# EXT_LED_RGB_NPN.net
KiCad netlist of a schematic drawn in EAGLE
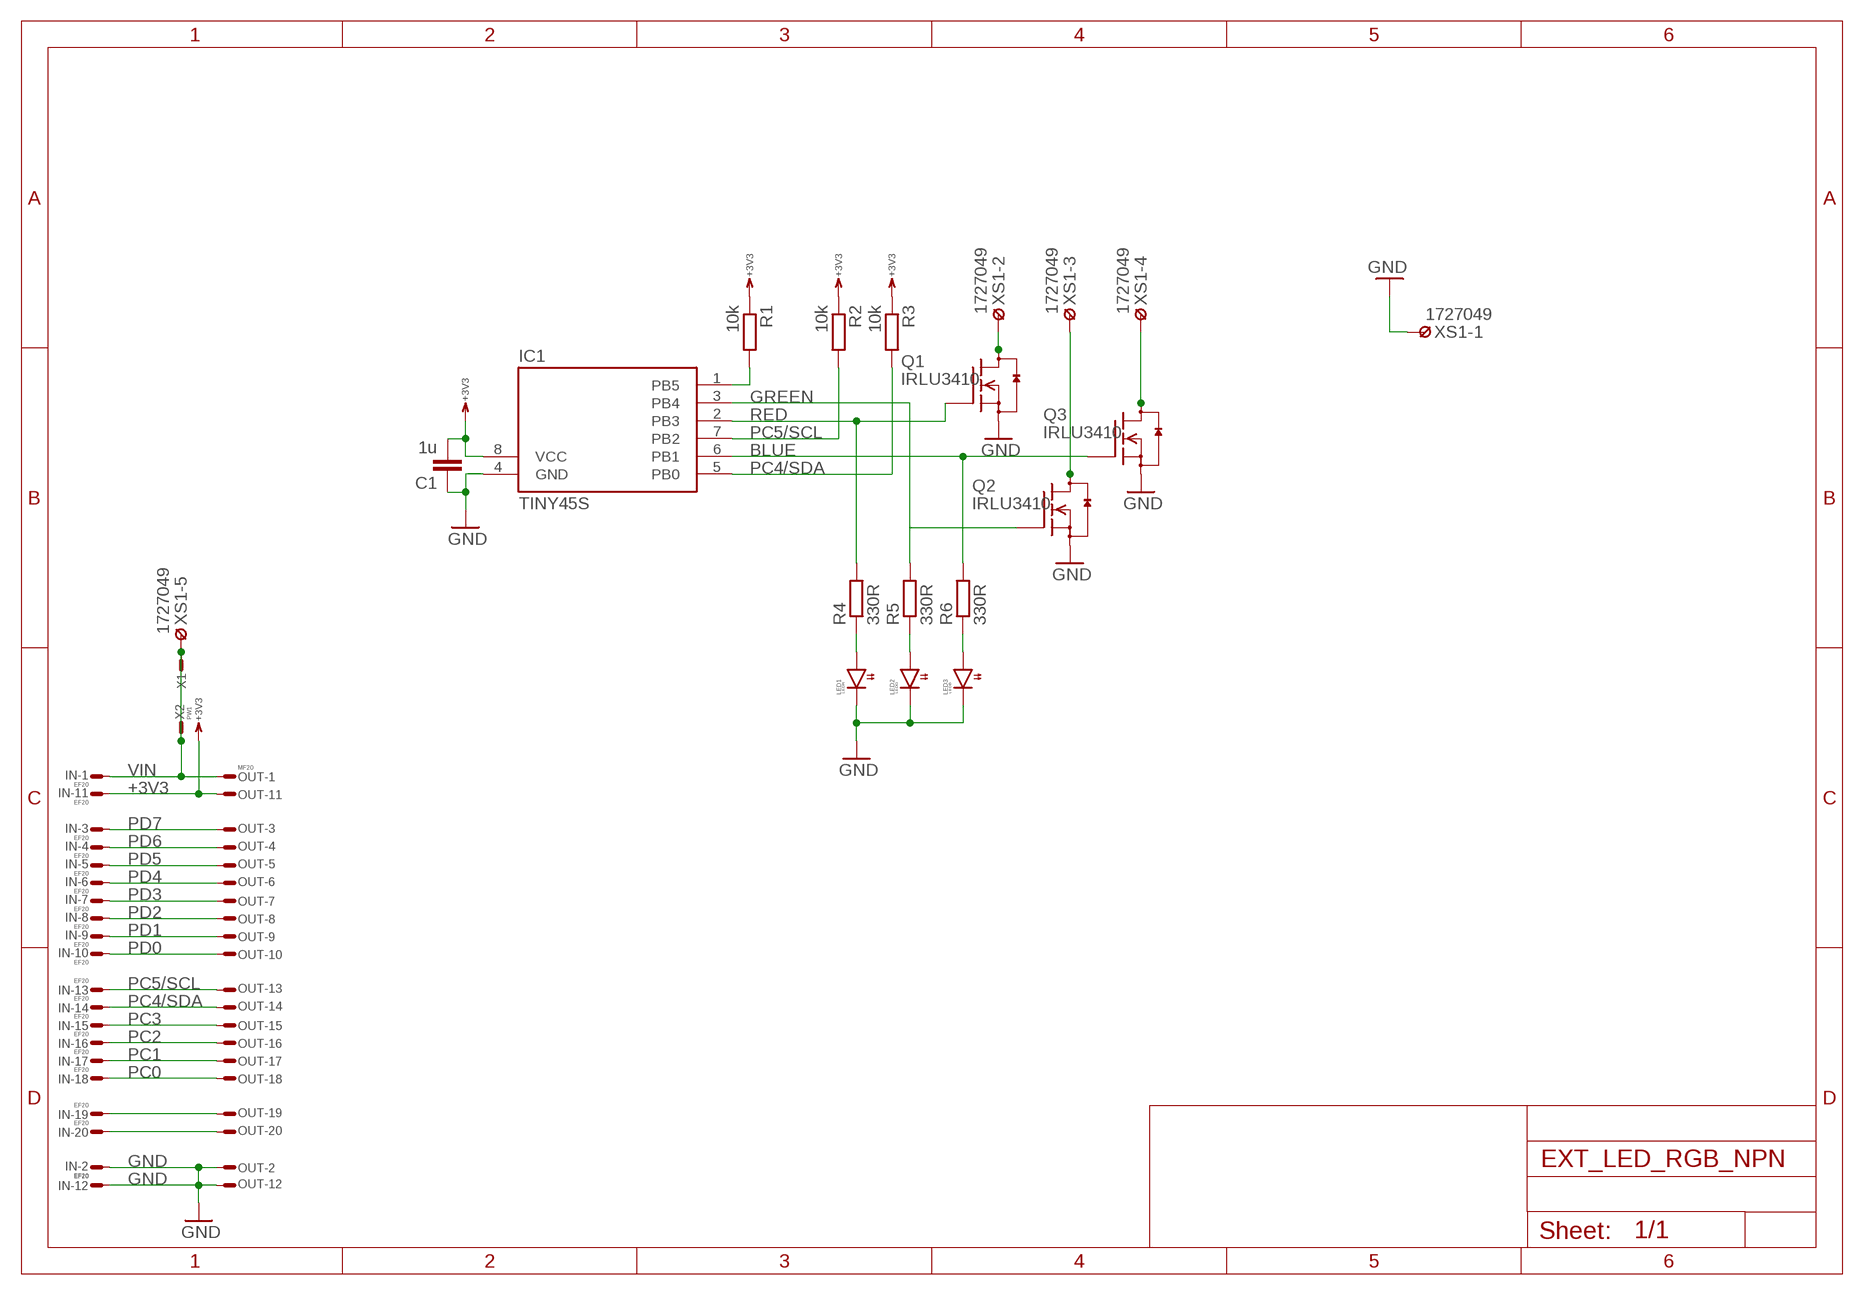
[diagram p0: schematic, sheet 1]

(export (version "E")
  (design (tool "Eeschema 10.0.6"))
  (components
    (comp (ref "C1")
      (value "1u")
      (footprint "eagle-import:0603")
      (libsource (lib "eagle-import") (part "C0603"))
    )
    (comp (ref "IC1")
      (value "TINY45S")
      (footprint "eagle-import:SOIC8")
      (libsource (lib "eagle-import") (part "TINY45S"))
    )
    (comp (ref "IN")
      (value "EF20")
      (footprint "eagle-import:FE10-2WSS")
      (libsource (lib "eagle-import") (part "FE20ELSS"))
    )
    (comp (ref "LED1")
      (value "LEDR")
      (footprint "eagle-import:1206")
      (libsource (lib "eagle-import") (part "LED1206"))
    )
    (comp (ref "LED2")
      (value "LEDG")
      (footprint "eagle-import:1206")
      (libsource (lib "eagle-import") (part "LED1206"))
    )
    (comp (ref "LED3")
      (value "LEDB")
      (footprint "eagle-import:1206")
      (libsource (lib "eagle-import") (part "LED1206"))
    )
    (comp (ref "OUT")
      (value "MF20")
      (footprint "eagle-import:ML20LS")
      (libsource (lib "eagle-import") (part "ML20?ELS"))
    )
    (comp (ref "Q1")
      (value "IRLU3410")
      (footprint "eagle-import:TO251AA")
      (libsource (lib "eagle-import") (part "FET-ND251"))
    )
    (comp (ref "Q2")
      (value "IRLU3410")
      (footprint "eagle-import:TO251AA")
      (libsource (lib "eagle-import") (part "FET-ND251"))
    )
    (comp (ref "Q3")
      (value "IRLU3410")
      (footprint "eagle-import:TO251AA")
      (libsource (lib "eagle-import") (part "FET-ND251"))
    )
    (comp (ref "R1")
      (value "10k")
      (footprint "eagle-import:0603")
      (libsource (lib "eagle-import") (part "R0603"))
    )
    (comp (ref "R2")
      (value "10k")
      (footprint "eagle-import:0603")
      (libsource (lib "eagle-import") (part "R0603"))
    )
    (comp (ref "R3")
      (value "10k")
      (footprint "eagle-import:0603")
      (libsource (lib "eagle-import") (part "R0603"))
    )
    (comp (ref "R4")
      (value "330R")
      (footprint "eagle-import:0603")
      (libsource (lib "eagle-import") (part "R0603"))
    )
    (comp (ref "R5")
      (value "330R")
      (footprint "eagle-import:0603")
      (libsource (lib "eagle-import") (part "R0603"))
    )
    (comp (ref "R6")
      (value "330R")
      (footprint "eagle-import:0603")
      (libsource (lib "eagle-import") (part "R0603"))
    )
    (comp (ref "X1")
      (value "WIREPADT1.6/0.9")
      (footprint "eagle-import:T1.6_0.9")
      (libsource (lib "eagle-import") (part "WIREPADT1.6/0.9"))
    )
    (comp (ref "X2")
      (value "PW1")
      (footprint "eagle-import:T1.6_0.9")
      (libsource (lib "eagle-import") (part "WIREPADT1.6/0.9"))
    )
    (comp (ref "XS1")
      (value "1727049")
      (footprint "eagle-import:1727049")
      (libsource (lib "eagle-import") (part "1727049"))
    )
  )
  (nets
    (net (code "1") (name "+3V3") (class "Default")
      (node (ref "C1") (pin "2") (pinfunction "2_2") (pintype "passive"))
      (node (ref "IC1") (pin "8") (pinfunction "VCC_8") (pintype "power_in"))
      (node (ref "IN") (pin "P$11") (pinfunction "S_P$11") (pintype "passive"))
      (node (ref "OUT") (pin "P$11") (pinfunction "S_P$11") (pintype "passive"))
      (node (ref "R1") (pin "1") (pinfunction "1_1") (pintype "passive"))
      (node (ref "R2") (pin "1") (pinfunction "1_1") (pintype "passive"))
      (node (ref "R3") (pin "1") (pinfunction "1_1") (pintype "passive"))
    )
    (net (code "2") (name "/BLUE") (class "Default")
      (node (ref "IC1") (pin "6") (pinfunction "PB1_6") (pintype "bidirectional"))
      (node (ref "Q3") (pin "1") (pinfunction "G_1") (pintype "passive"))
      (node (ref "R6") (pin "2") (pinfunction "2_2") (pintype "passive"))
    )
    (net (code "3") (name "/GREEN") (class "Default")
      (node (ref "IC1") (pin "3") (pinfunction "PB4_3") (pintype "bidirectional"))
      (node (ref "Q2") (pin "1") (pinfunction "G_1") (pintype "passive"))
      (node (ref "R5") (pin "2") (pinfunction "2_2") (pintype "passive"))
    )
    (net (code "4") (name "/PC0") (class "Default")
      (node (ref "IN") (pin "P$18") (pinfunction "S_P$18") (pintype "passive"))
      (node (ref "OUT") (pin "P$18") (pinfunction "S_P$18") (pintype "passive"))
    )
    (net (code "5") (name "/PC1") (class "Default")
      (node (ref "IN") (pin "P$17") (pinfunction "S_P$17") (pintype "passive"))
      (node (ref "OUT") (pin "P$17") (pinfunction "S_P$17") (pintype "passive"))
    )
    (net (code "6") (name "/PC2") (class "Default")
      (node (ref "IN") (pin "P$16") (pinfunction "S_P$16") (pintype "passive"))
      (node (ref "OUT") (pin "P$16") (pinfunction "S_P$16") (pintype "passive"))
    )
    (net (code "7") (name "/PC3") (class "Default")
      (node (ref "IN") (pin "P$15") (pinfunction "S_P$15") (pintype "passive"))
      (node (ref "OUT") (pin "P$15") (pinfunction "S_P$15") (pintype "passive"))
    )
    (net (code "8") (name "/PC4{slash}SDA") (class "Default")
      (node (ref "IC1") (pin "5") (pinfunction "PB0_5") (pintype "bidirectional"))
      (node (ref "IN") (pin "P$14") (pinfunction "S_P$14") (pintype "passive"))
      (node (ref "OUT") (pin "P$14") (pinfunction "S_P$14") (pintype "passive"))
      (node (ref "R3") (pin "2") (pinfunction "2_2") (pintype "passive"))
    )
    (net (code "9") (name "/PC5{slash}SCL") (class "Default")
      (node (ref "IC1") (pin "7") (pinfunction "PB2_7") (pintype "bidirectional"))
      (node (ref "IN") (pin "P$13") (pinfunction "S_P$13") (pintype "passive"))
      (node (ref "OUT") (pin "P$13") (pinfunction "S_P$13") (pintype "passive"))
      (node (ref "R2") (pin "2") (pinfunction "2_2") (pintype "passive"))
    )
    (net (code "10") (name "/PD0") (class "Default")
      (node (ref "IN") (pin "P$10") (pinfunction "S_P$10") (pintype "passive"))
      (node (ref "OUT") (pin "P$10") (pinfunction "S_P$10") (pintype "passive"))
    )
    (net (code "11") (name "/PD1") (class "Default")
      (node (ref "IN") (pin "P$9") (pinfunction "S_P$9") (pintype "passive"))
      (node (ref "OUT") (pin "P$9") (pinfunction "S_P$9") (pintype "passive"))
    )
    (net (code "12") (name "/PD2") (class "Default")
      (node (ref "IN") (pin "P$8") (pinfunction "S_P$8") (pintype "passive"))
      (node (ref "OUT") (pin "P$8") (pinfunction "S_P$8") (pintype "passive"))
    )
    (net (code "13") (name "/PD3") (class "Default")
      (node (ref "IN") (pin "P$7") (pinfunction "S_P$7") (pintype "passive"))
      (node (ref "OUT") (pin "P$7") (pinfunction "S_P$7") (pintype "passive"))
    )
    (net (code "14") (name "/PD4") (class "Default")
      (node (ref "IN") (pin "P$6") (pinfunction "S_P$6") (pintype "passive"))
      (node (ref "OUT") (pin "P$6") (pinfunction "S_P$6") (pintype "passive"))
    )
    (net (code "15") (name "/PD5") (class "Default")
      (node (ref "IN") (pin "P$5") (pinfunction "S_P$5") (pintype "passive"))
      (node (ref "OUT") (pin "P$5") (pinfunction "S_P$5") (pintype "passive"))
    )
    (net (code "16") (name "/PD6") (class "Default")
      (node (ref "IN") (pin "P$4") (pinfunction "S_P$4") (pintype "passive"))
      (node (ref "OUT") (pin "P$4") (pinfunction "S_P$4") (pintype "passive"))
    )
    (net (code "17") (name "/PD7") (class "Default")
      (node (ref "IN") (pin "P$3") (pinfunction "S_P$3") (pintype "passive"))
      (node (ref "OUT") (pin "P$3") (pinfunction "S_P$3") (pintype "passive"))
    )
    (net (code "18") (name "/RED") (class "Default")
      (node (ref "IC1") (pin "2") (pinfunction "PB3_2") (pintype "bidirectional"))
      (node (ref "Q1") (pin "1") (pinfunction "G_1") (pintype "passive"))
      (node (ref "R4") (pin "2") (pinfunction "2_2") (pintype "passive"))
    )
    (net (code "19") (name "/VIN") (class "Default")
      (node (ref "IN") (pin "P$1") (pinfunction "S_P$1") (pintype "passive"))
      (node (ref "OUT") (pin "P$1") (pinfunction "S_P$1") (pintype "passive"))
      (node (ref "X1") (pin "1") (pinfunction "S_1") (pintype "passive"))
      (node (ref "X2") (pin "1") (pinfunction "S_1") (pintype "passive"))
      (node (ref "XS1") (pin "5") (pinfunction "K_5") (pintype "passive"))
    )
    (net (code "20") (name "GND") (class "Default")
      (node (ref "C1") (pin "1") (pinfunction "1_1") (pintype "passive"))
      (node (ref "IC1") (pin "4") (pinfunction "GND_4") (pintype "power_in"))
      (node (ref "IN") (pin "P$12") (pinfunction "S_P$12") (pintype "passive"))
      (node (ref "IN") (pin "P$2") (pinfunction "S_P$2") (pintype "passive"))
      (node (ref "LED1") (pin "2") (pinfunction "C_2") (pintype "bidirectional"))
      (node (ref "LED2") (pin "2") (pinfunction "C_2") (pintype "bidirectional"))
      (node (ref "LED3") (pin "2") (pinfunction "C_2") (pintype "bidirectional"))
      (node (ref "OUT") (pin "P$12") (pinfunction "S_P$12") (pintype "passive"))
      (node (ref "OUT") (pin "P$2") (pinfunction "S_P$2") (pintype "passive"))
      (node (ref "Q1") (pin "3") (pinfunction "S_3") (pintype "passive"))
      (node (ref "Q2") (pin "3") (pinfunction "S_3") (pintype "passive"))
      (node (ref "Q3") (pin "3") (pinfunction "S_3") (pintype "passive"))
      (node (ref "XS1") (pin "1") (pinfunction "K_1") (pintype "passive"))
    )
    (net (code "21") (name "Net-(IC1-PB5)") (class "Default")
      (node (ref "IC1") (pin "1") (pinfunction "PB5_1") (pintype "bidirectional"))
      (node (ref "R1") (pin "2") (pinfunction "2_2") (pintype "passive"))
    )
    (net (code "22") (name "Net-(INK-S)") (class "Default")
      (node (ref "IN") (pin "P$19") (pinfunction "S_P$19") (pintype "passive"))
      (node (ref "OUT") (pin "P$19") (pinfunction "S_P$19") (pintype "passive"))
    )
    (net (code "23") (name "Net-(INM-S)") (class "Default")
      (node (ref "IN") (pin "P$20") (pinfunction "S_P$20") (pintype "passive"))
      (node (ref "OUT") (pin "P$20") (pinfunction "S_P$20") (pintype "passive"))
    )
    (net (code "24") (name "Net-(LED1-A)") (class "Default")
      (node (ref "LED1") (pin "1") (pinfunction "A_1") (pintype "bidirectional"))
      (node (ref "R4") (pin "1") (pinfunction "1_1") (pintype "passive"))
    )
    (net (code "25") (name "Net-(LED2-A)") (class "Default")
      (node (ref "LED2") (pin "1") (pinfunction "A_1") (pintype "bidirectional"))
      (node (ref "R5") (pin "1") (pinfunction "1_1") (pintype "passive"))
    )
    (net (code "26") (name "Net-(LED3-A)") (class "Default")
      (node (ref "LED3") (pin "1") (pinfunction "A_1") (pintype "bidirectional"))
      (node (ref "R6") (pin "1") (pinfunction "1_1") (pintype "passive"))
    )
    (net (code "27") (name "Net-(Q1-D)") (class "Default")
      (node (ref "Q1") (pin "2") (pinfunction "D_2") (pintype "passive"))
      (node (ref "XS1") (pin "2") (pinfunction "K_2") (pintype "passive"))
    )
    (net (code "28") (name "Net-(Q2-D)") (class "Default")
      (node (ref "Q2") (pin "2") (pinfunction "D_2") (pintype "passive"))
      (node (ref "XS1") (pin "3") (pinfunction "K_3") (pintype "passive"))
    )
    (net (code "29") (name "Net-(Q3-D)") (class "Default")
      (node (ref "Q3") (pin "2") (pinfunction "D_2") (pintype "passive"))
      (node (ref "XS1") (pin "4") (pinfunction "K_4") (pintype "passive"))
    )
  )
)
